# interface_dac_sma_feedback_3PS_ADC_detec.net
KiCad netlist of a schematic drawn in EAGLE
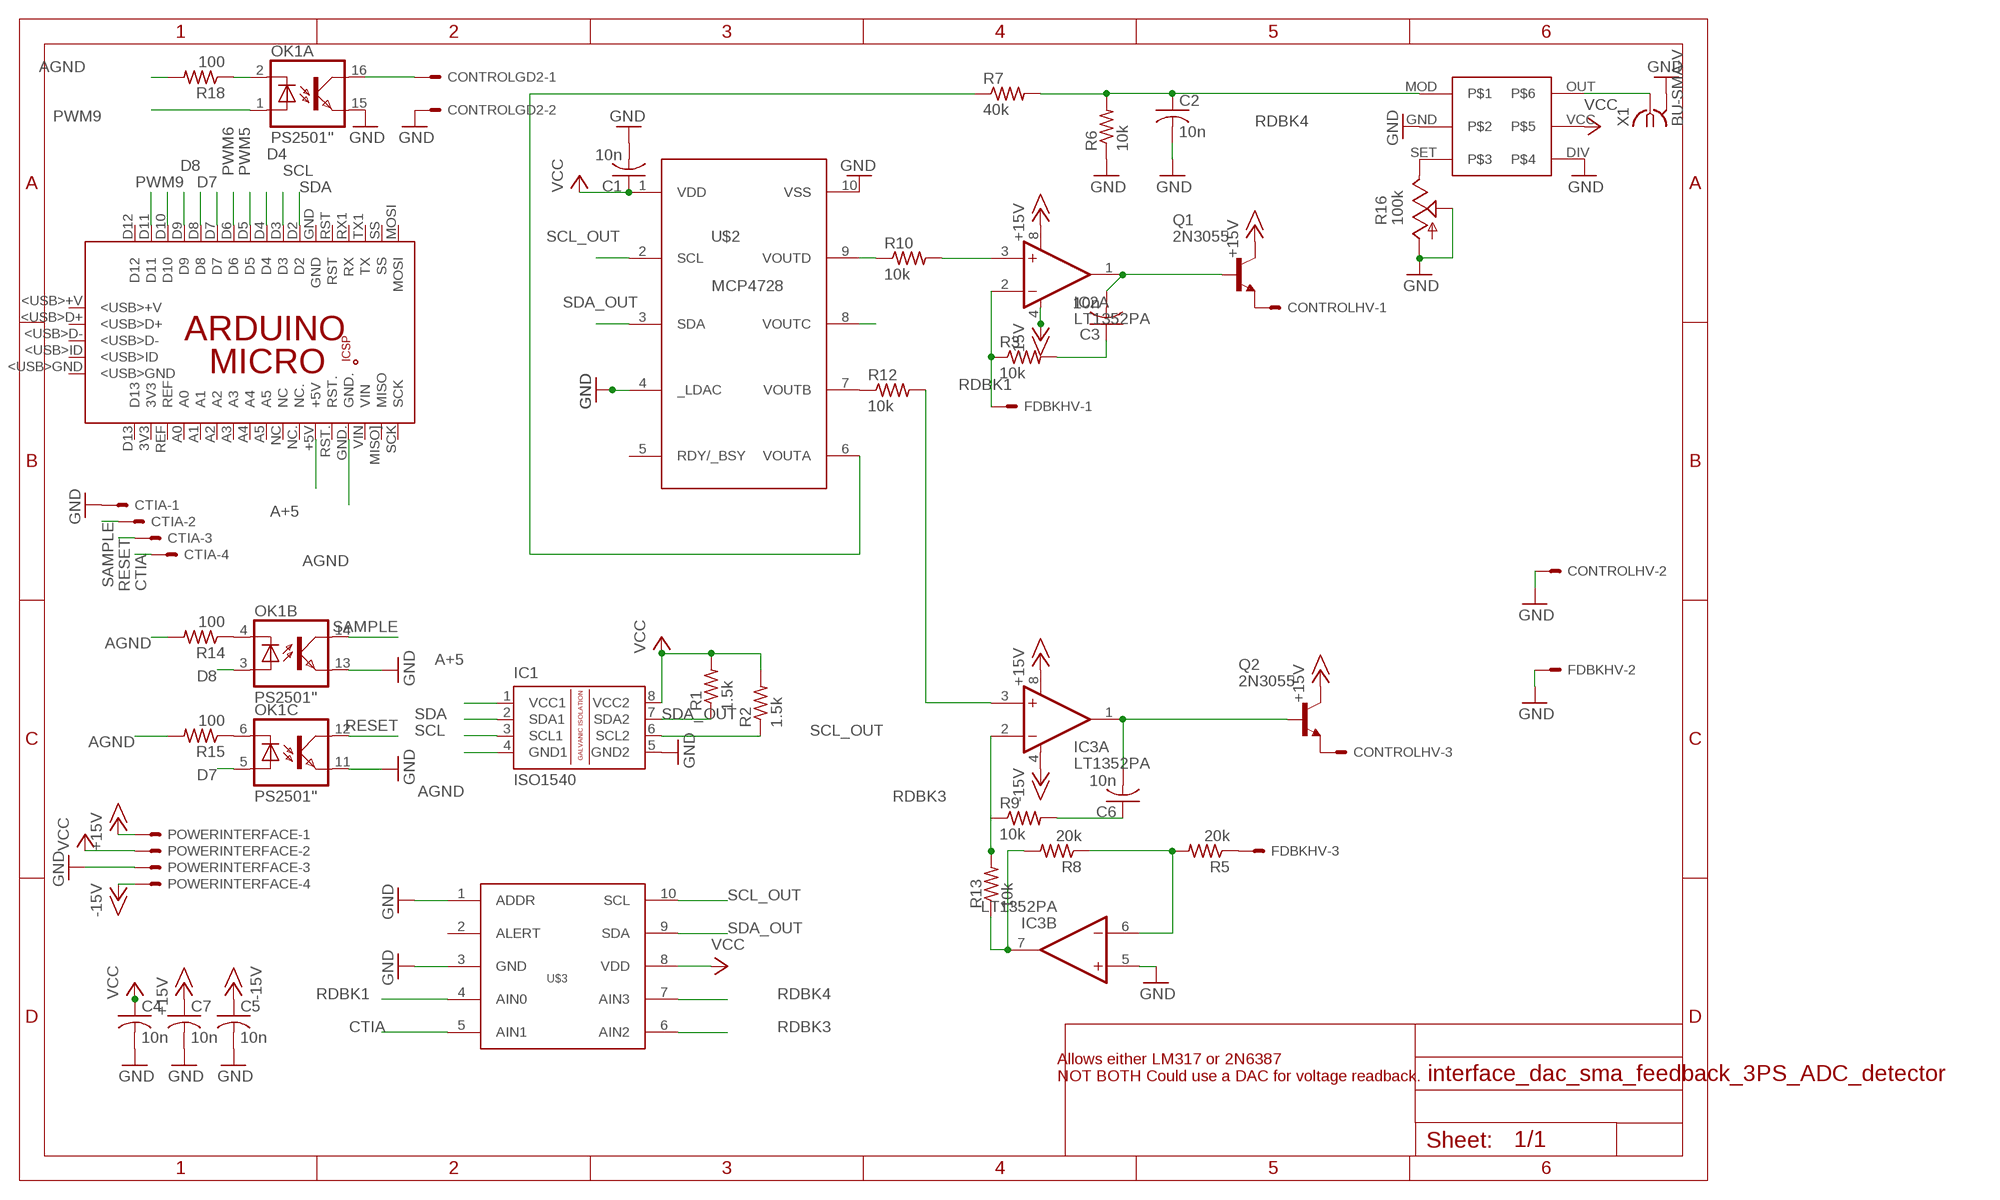
[diagram p0: schematic, sheet 1]

(export (version "E")
  (design (tool "Eeschema 10.0.6"))
  (components
    (comp (ref "C1")
      (value "10n")
      (footprint "eagle-import:C050-024X044")
      (libsource (lib "eagle-import") (part "C-US050-024X044"))
    )
    (comp (ref "C2")
      (value "10n")
      (footprint "eagle-import:C050-024X044")
      (libsource (lib "eagle-import") (part "resistor_C-US050-024X044"))
    )
    (comp (ref "C3")
      (value "10n")
      (footprint "eagle-import:C050-024X044")
      (libsource (lib "eagle-import") (part "resistor_C-US050-024X044"))
    )
    (comp (ref "C4")
      (value "10n")
      (footprint "eagle-import:C050-024X044")
      (libsource (lib "eagle-import") (part "resistor_C-US050-024X044"))
    )
    (comp (ref "C5")
      (value "10n")
      (footprint "eagle-import:C050-024X044")
      (libsource (lib "eagle-import") (part "resistor_C-US050-024X044"))
    )
    (comp (ref "C6")
      (value "10n")
      (footprint "eagle-import:C050-024X044")
      (libsource (lib "eagle-import") (part "resistor_C-US050-024X044"))
    )
    (comp (ref "C7")
      (value "10n")
      (footprint "eagle-import:C050-024X044")
      (libsource (lib "eagle-import") (part "resistor_C-US050-024X044"))
    )
    (comp (ref "CONTROLGD2")
      (value "KK-156-2")
      (footprint "eagle-import:KK-156-2")
      (libsource (lib "eagle-import") (part "KK-156-2"))
    )
    (comp (ref "CONTROLHV")
      (value "KK-156-3")
      (footprint "eagle-import:KK-156-3")
      (libsource (lib "eagle-import") (part "KK-156-3"))
    )
    (comp (ref "CTIA")
      (value "KK-156-4")
      (footprint "eagle-import:KK-156-4")
      (libsource (lib "eagle-import") (part "KK-156-4"))
    )
    (comp (ref "FDBKHV")
      (value "KK-156-3")
      (footprint "eagle-import:KK-156-3")
      (libsource (lib "eagle-import") (part "KK-156-3"))
    )
    (comp (ref "IC1")
      (value "ISO1540")
      (footprint "eagle-import:DIL08")
      (libsource (lib "eagle-import") (part "ISO1540"))
    )
    (comp (ref "IC2")
      (value "LT1352PA")
      (footprint "eagle-import:DIL08")
      (libsource (lib "eagle-import") (part "LT1352PA"))
    )
    (comp (ref "IC3")
      (value "LT1352PA")
      (footprint "eagle-import:DIL08")
      (libsource (lib "eagle-import") (part "LT1352PA"))
    )
    (comp (ref "OK1")
      (value "PS2501\"")
      (footprint "eagle-import:DIL16")
      (libsource (lib "eagle-import") (part "PS2501{dblquote}"))
    )
    (comp (ref "PCB1")
      (value "ARDUINO_MICRO")
      (footprint "eagle-import:ARDUINO_MICRO")
      (libsource (lib "eagle-import") (part "ARDUINO_MICRO"))
    )
    (comp (ref "POWERINTERFACE")
      (value "KK-156-4")
      (footprint "eagle-import:KK-156-4")
      (libsource (lib "eagle-import") (part "KK-156-4"))
    )
    (comp (ref "Q1")
      (value "2N3055")
      (footprint "eagle-import:TO3")
      (libsource (lib "eagle-import") (part "2N3055"))
    )
    (comp (ref "Q2")
      (value "2N3055")
      (footprint "eagle-import:TO3")
      (libsource (lib "eagle-import") (part "2N3055"))
    )
    (comp (ref "R1")
      (value "1.5k")
      (footprint "eagle-import:0207_12")
      (libsource (lib "eagle-import") (part "resistor_R-US_0207/12"))
    )
    (comp (ref "R2")
      (value "1.5k")
      (footprint "eagle-import:0207_12")
      (libsource (lib "eagle-import") (part "resistor_R-US_0207/12"))
    )
    (comp (ref "R3")
      (value "10k")
      (footprint "eagle-import:0207_12")
      (libsource (lib "eagle-import") (part "resistor_R-US_0207/12"))
    )
    (comp (ref "R5")
      (value "20k")
      (footprint "eagle-import:0207_12")
      (libsource (lib "eagle-import") (part "resistor_R-US_0207/12"))
    )
    (comp (ref "R6")
      (value "10k")
      (footprint "eagle-import:0207_12")
      (libsource (lib "eagle-import") (part "resistor_R-US_0207/12"))
    )
    (comp (ref "R7")
      (value "40k")
      (footprint "eagle-import:0207_12")
      (libsource (lib "eagle-import") (part "resistor_R-US_0207/12"))
    )
    (comp (ref "R8")
      (value "20k")
      (footprint "eagle-import:0207_12")
      (libsource (lib "eagle-import") (part "resistor_R-US_0207/12"))
    )
    (comp (ref "R9")
      (value "10k")
      (footprint "eagle-import:0207_12")
      (libsource (lib "eagle-import") (part "resistor_R-US_0207/12"))
    )
    (comp (ref "R10")
      (value "10k")
      (footprint "eagle-import:0207_12")
      (libsource (lib "eagle-import") (part "resistor_R-US_0207/12"))
    )
    (comp (ref "R12")
      (value "10k")
      (footprint "eagle-import:0207_12")
      (libsource (lib "eagle-import") (part "resistor_R-US_0207/12"))
    )
    (comp (ref "R13")
      (value "10k")
      (footprint "eagle-import:0207_12")
      (libsource (lib "eagle-import") (part "resistor_R-US_0207/12"))
    )
    (comp (ref "R14")
      (value "100")
      (footprint "eagle-import:0207_12")
      (libsource (lib "eagle-import") (part "R-US_0207/12"))
    )
    (comp (ref "R15")
      (value "100")
      (footprint "eagle-import:0207_12")
      (libsource (lib "eagle-import") (part "R-US_0207/12"))
    )
    (comp (ref "R16")
      (value "100k")
      (footprint "eagle-import:SP19L")
      (libsource (lib "eagle-import") (part "TRIM_US-B90P"))
    )
    (comp (ref "R18")
      (value "100")
      (footprint "eagle-import:0207_12")
      (libsource (lib "eagle-import") (part "R-US_0207/12"))
    )
    (comp (ref "U$1")
      (value "LTC6992")
      (footprint "eagle-import:DIL06")
      (libsource (lib "eagle-import") (part "LTC6992"))
    )
    (comp (ref "U$2")
      (value "MCP4728DIL")
      (footprint "eagle-import:DIL10")
      (libsource (lib "eagle-import") (part "MCP4728DIL"))
    )
    (comp (ref "U$3")
      (value "ADS1015DIL")
      (footprint "eagle-import:DIL10")
      (libsource (lib "eagle-import") (part "ADS1015DIL"))
    )
    (comp (ref "X1")
      (value "BU-SMA-V")
      (footprint "eagle-import:BU-SMA-V")
      (libsource (lib "eagle-import") (part "BU-SMA-V"))
    )
  )
  (nets
    (net (code "1") (name "+15V") (class "Default")
      (node (ref "C7") (pin "1") (pinfunction "1_1") (pintype "passive"))
      (node (ref "IC2") (pin "8") (pinfunction "V+_8") (pintype "power_in"))
      (node (ref "IC3") (pin "8") (pinfunction "V+_8") (pintype "power_in"))
      (node (ref "POWERINTERFACE") (pin "1") (pinfunction "S_1") (pintype "passive"))
      (node (ref "Q1") (pin "C") (pinfunction "C_C") (pintype "passive"))
      (node (ref "Q1") (pin "C/") (pinfunction "C_C/") (pintype "passive"))
      (node (ref "Q2") (pin "C") (pinfunction "C_C") (pintype "passive"))
      (node (ref "Q2") (pin "C/") (pinfunction "C_C/") (pintype "passive"))
    )
    (net (code "2") (name "-15V") (class "Default")
      (node (ref "C5") (pin "1") (pinfunction "1_1") (pintype "passive"))
      (node (ref "IC2") (pin "4") (pinfunction "V-_4") (pintype "power_in"))
      (node (ref "IC3") (pin "4") (pinfunction "V-_4") (pintype "power_in"))
      (node (ref "POWERINTERFACE") (pin "4") (pinfunction "S_4") (pintype "passive"))
    )
    (net (code "3") (name "/A+5") (class "Default")
      (node (ref "IC1") (pin "1") (pinfunction "VCC1_1") (pintype "input"))
      (node (ref "PCB1") (pin "+5V") (pinfunction "+5V_+5V") (pintype "bidirectional"))
    )
    (net (code "4") (name "/AGND") (class "Default")
      (node (ref "IC1") (pin "4") (pinfunction "GND1_4") (pintype "input"))
      (node (ref "PCB1") (pin "GND.") (pinfunction "GND._GND.") (pintype "bidirectional"))
      (node (ref "R14") (pin "2") (pinfunction "2_2") (pintype "passive"))
      (node (ref "R15") (pin "2") (pinfunction "2_2") (pintype "passive"))
      (node (ref "R18") (pin "2") (pinfunction "2_2") (pintype "passive"))
    )
    (net (code "5") (name "/CTIA") (class "Default")
      (node (ref "CTIA") (pin "4") (pinfunction "S_4") (pintype "passive"))
      (node (ref "U$3") (pin "5") (pinfunction "AIN1_5") (pintype "bidirectional"))
    )
    (net (code "6") (name "/D4") (class "Default")
      (node (ref "PCB1") (pin "D4") (pinfunction "D4_D4") (pintype "bidirectional"))
    )
    (net (code "7") (name "/D7") (class "Default")
      (node (ref "OK1") (pin "5") (pinfunction "A_5") (pintype "passive"))
      (node (ref "PCB1") (pin "D7") (pinfunction "D7_D7") (pintype "bidirectional"))
    )
    (net (code "8") (name "/D8") (class "Default")
      (node (ref "OK1") (pin "3") (pinfunction "A_3") (pintype "passive"))
      (node (ref "PCB1") (pin "D8") (pinfunction "D8_D8") (pintype "bidirectional"))
    )
    (net (code "9") (name "/PWM5") (class "Default")
      (node (ref "PCB1") (pin "D5") (pinfunction "D5_D5") (pintype "bidirectional"))
    )
    (net (code "10") (name "/PWM6") (class "Default")
      (node (ref "PCB1") (pin "D6") (pinfunction "D6_D6") (pintype "bidirectional"))
    )
    (net (code "11") (name "/PWM9") (class "Default")
      (node (ref "OK1") (pin "1") (pinfunction "A_1") (pintype "passive"))
      (node (ref "PCB1") (pin "D9") (pinfunction "D9_D9") (pintype "bidirectional"))
    )
    (net (code "12") (name "/RDBK1") (class "Default")
      (node (ref "FDBKHV") (pin "1") (pinfunction "S_1") (pintype "passive"))
      (node (ref "IC2") (pin "2") (pinfunction "-IN_2") (pintype "input"))
      (node (ref "R3") (pin "1") (pinfunction "1_1") (pintype "passive"))
      (node (ref "U$3") (pin "4") (pinfunction "AIN0_4") (pintype "bidirectional"))
    )
    (net (code "13") (name "/RDBK3") (class "Default")
      (node (ref "IC3") (pin "2") (pinfunction "-IN_2") (pintype "input"))
      (node (ref "R13") (pin "2") (pinfunction "2_2") (pintype "passive"))
      (node (ref "R9") (pin "1") (pinfunction "1_1") (pintype "passive"))
      (node (ref "U$3") (pin "6") (pinfunction "AIN2_6") (pintype "bidirectional"))
    )
    (net (code "14") (name "/RDBK4") (class "Default")
      (node (ref "C2") (pin "1") (pinfunction "1_1") (pintype "passive"))
      (node (ref "R6") (pin "2") (pinfunction "2_2") (pintype "passive"))
      (node (ref "R7") (pin "2") (pinfunction "2_2") (pintype "passive"))
      (node (ref "U$1") (pin "MOD") (pinfunction "P$1_MOD") (pintype "bidirectional"))
      (node (ref "U$3") (pin "7") (pinfunction "AIN3_7") (pintype "bidirectional"))
    )
    (net (code "15") (name "/RESET") (class "Default")
      (node (ref "CTIA") (pin "3") (pinfunction "S_3") (pintype "passive"))
      (node (ref "OK1") (pin "12") (pinfunction "COL_12") (pintype "passive"))
    )
    (net (code "16") (name "/SAMPLE") (class "Default")
      (node (ref "CTIA") (pin "2") (pinfunction "S_2") (pintype "passive"))
      (node (ref "OK1") (pin "14") (pinfunction "COL_14") (pintype "passive"))
    )
    (net (code "17") (name "/SCL") (class "Default")
      (node (ref "IC1") (pin "3") (pinfunction "SCL1_3") (pintype "input"))
      (node (ref "PCB1") (pin "D3") (pinfunction "D3_D3") (pintype "bidirectional"))
    )
    (net (code "18") (name "/SCL_OUT") (class "Default")
      (node (ref "IC1") (pin "6") (pinfunction "SCL2_6") (pintype "input"))
      (node (ref "R2") (pin "1") (pinfunction "1_1") (pintype "passive"))
      (node (ref "U$2") (pin "2") (pinfunction "SCL_2") (pintype "bidirectional"))
      (node (ref "U$3") (pin "10") (pinfunction "SCL_10") (pintype "bidirectional"))
    )
    (net (code "19") (name "/SDA") (class "Default")
      (node (ref "IC1") (pin "2") (pinfunction "SDA1_2") (pintype "input"))
      (node (ref "PCB1") (pin "D2") (pinfunction "D2_D2") (pintype "bidirectional"))
    )
    (net (code "20") (name "/SDA_OUT") (class "Default")
      (node (ref "IC1") (pin "7") (pinfunction "SDA2_7") (pintype "input"))
      (node (ref "R1") (pin "1") (pinfunction "1_1") (pintype "passive"))
      (node (ref "U$2") (pin "3") (pinfunction "SDA_3") (pintype "bidirectional"))
      (node (ref "U$3") (pin "9") (pinfunction "SDA_9") (pintype "bidirectional"))
    )
    (net (code "21") (name "GND") (class "Default")
      (node (ref "C1") (pin "2") (pinfunction "2_2") (pintype "passive"))
      (node (ref "C2") (pin "2") (pinfunction "2_2") (pintype "passive"))
      (node (ref "C4") (pin "2") (pinfunction "2_2") (pintype "passive"))
      (node (ref "C5") (pin "2") (pinfunction "2_2") (pintype "passive"))
      (node (ref "C7") (pin "2") (pinfunction "2_2") (pintype "passive"))
      (node (ref "CONTROLGD2") (pin "2") (pinfunction "S_2") (pintype "passive"))
      (node (ref "CONTROLHV") (pin "2") (pinfunction "S_2") (pintype "passive"))
      (node (ref "CTIA") (pin "1") (pinfunction "S_1") (pintype "passive"))
      (node (ref "FDBKHV") (pin "2") (pinfunction "S_2") (pintype "passive"))
      (node (ref "IC1") (pin "5") (pinfunction "GND2_5") (pintype "input"))
      (node (ref "IC3") (pin "5") (pinfunction "+IN_5") (pintype "input"))
      (node (ref "OK1") (pin "11") (pinfunction "EMI_11") (pintype "passive"))
      (node (ref "OK1") (pin "13") (pinfunction "EMI_13") (pintype "passive"))
      (node (ref "OK1") (pin "15") (pinfunction "EMI_15") (pintype "passive"))
      (node (ref "POWERINTERFACE") (pin "3") (pinfunction "S_3") (pintype "passive"))
      (node (ref "R16") (pin "A") (pinfunction "A_A") (pintype "passive"))
      (node (ref "R16") (pin "S") (pinfunction "S_S") (pintype "passive"))
      (node (ref "R6") (pin "1") (pinfunction "1_1") (pintype "passive"))
      (node (ref "U$1") (pin "DIV") (pinfunction "P$4_DIV") (pintype "bidirectional"))
      (node (ref "U$1") (pin "GND") (pinfunction "P$2_GND") (pintype "bidirectional"))
      (node (ref "U$2") (pin "10") (pinfunction "VSS_10") (pintype "bidirectional"))
      (node (ref "U$2") (pin "4") (pinfunction "_LDAC_4") (pintype "bidirectional"))
      (node (ref "U$3") (pin "1") (pinfunction "ADDR_1") (pintype "bidirectional"))
      (node (ref "U$3") (pin "3") (pinfunction "GND_3") (pintype "bidirectional"))
      (node (ref "X1") (pin "2") (pinfunction "2_2") (pintype "passive"))
      (node (ref "X1") (pin "3") (pinfunction "2_3") (pintype "passive"))
      (node (ref "X1") (pin "4") (pinfunction "2_4") (pintype "passive"))
      (node (ref "X1") (pin "5") (pinfunction "2_5") (pintype "passive"))
    )
    (net (code "22") (name "Net-(C3-Pad1)") (class "Default")
      (node (ref "C3") (pin "1") (pinfunction "1_1") (pintype "passive"))
      (node (ref "R3") (pin "2") (pinfunction "2_2") (pintype "passive"))
    )
    (net (code "23") (name "Net-(C6-Pad1)") (class "Default")
      (node (ref "C6") (pin "1") (pinfunction "1_1") (pintype "passive"))
      (node (ref "R9") (pin "2") (pinfunction "2_2") (pintype "passive"))
    )
    (net (code "24") (name "Net-(CONTROLGD2A-S)") (class "Default")
      (node (ref "CONTROLGD2") (pin "1") (pinfunction "S_1") (pintype "passive"))
      (node (ref "OK1") (pin "16") (pinfunction "COL_16") (pintype "passive"))
    )
    (net (code "25") (name "Net-(CONTROLHVA-S)") (class "Default")
      (node (ref "CONTROLHV") (pin "1") (pinfunction "S_1") (pintype "passive"))
      (node (ref "Q1") (pin "E") (pinfunction "E_E") (pintype "passive"))
    )
    (net (code "26") (name "Net-(CONTROLHVC-S)") (class "Default")
      (node (ref "CONTROLHV") (pin "3") (pinfunction "S_3") (pintype "passive"))
      (node (ref "Q2") (pin "E") (pinfunction "E_E") (pintype "passive"))
    )
    (net (code "27") (name "Net-(FDBKHVC-S)") (class "Default")
      (node (ref "FDBKHV") (pin "3") (pinfunction "S_3") (pintype "passive"))
      (node (ref "R5") (pin "1") (pinfunction "1_1") (pintype "passive"))
    )
    (net (code "28") (name "Net-(IC2A-+IN)") (class "Default")
      (node (ref "IC2") (pin "3") (pinfunction "+IN_3") (pintype "input"))
      (node (ref "R10") (pin "2") (pinfunction "2_2") (pintype "passive"))
    )
    (net (code "29") (name "Net-(IC2A-OUT)") (class "Default")
      (node (ref "C3") (pin "2") (pinfunction "2_2") (pintype "passive"))
      (node (ref "IC2") (pin "1") (pinfunction "OUT_1") (pintype "output"))
      (node (ref "Q1") (pin "B") (pinfunction "B_B") (pintype "passive"))
    )
    (net (code "30") (name "Net-(IC3A-+IN)") (class "Default")
      (node (ref "IC3") (pin "3") (pinfunction "+IN_3") (pintype "input"))
      (node (ref "R12") (pin "2") (pinfunction "2_2") (pintype "passive"))
    )
    (net (code "31") (name "Net-(IC3A-OUT)") (class "Default")
      (node (ref "C6") (pin "2") (pinfunction "2_2") (pintype "passive"))
      (node (ref "IC3") (pin "1") (pinfunction "OUT_1") (pintype "output"))
      (node (ref "Q2") (pin "B") (pinfunction "B_B") (pintype "passive"))
    )
    (net (code "32") (name "Net-(IC3B--IN)") (class "Default")
      (node (ref "IC3") (pin "6") (pinfunction "-IN_6") (pintype "input"))
      (node (ref "R5") (pin "2") (pinfunction "2_2") (pintype "passive"))
      (node (ref "R8") (pin "1") (pinfunction "1_1") (pintype "passive"))
    )
    (net (code "33") (name "Net-(IC3B-OUT)") (class "Default")
      (node (ref "IC3") (pin "7") (pinfunction "OUT_7") (pintype "output"))
      (node (ref "R13") (pin "1") (pinfunction "1_1") (pintype "passive"))
      (node (ref "R8") (pin "2") (pinfunction "2_2") (pintype "passive"))
    )
    (net (code "34") (name "Net-(OK1A-C)") (class "Default")
      (node (ref "OK1") (pin "2") (pinfunction "C_2") (pintype "passive"))
      (node (ref "R18") (pin "1") (pinfunction "1_1") (pintype "passive"))
    )
    (net (code "35") (name "Net-(OK1B-C)") (class "Default")
      (node (ref "OK1") (pin "4") (pinfunction "C_4") (pintype "passive"))
      (node (ref "R14") (pin "1") (pinfunction "1_1") (pintype "passive"))
    )
    (net (code "36") (name "Net-(OK1C-C)") (class "Default")
      (node (ref "OK1") (pin "6") (pinfunction "C_6") (pintype "passive"))
      (node (ref "R15") (pin "1") (pinfunction "1_1") (pintype "passive"))
    )
    (net (code "37") (name "Net-(U$1-P$3)") (class "Default")
      (node (ref "R16") (pin "E") (pinfunction "E_E") (pintype "passive"))
      (node (ref "U$1") (pin "SET") (pinfunction "P$3_SET") (pintype "bidirectional"))
    )
    (net (code "38") (name "Net-(U$1-P$6)") (class "Default")
      (node (ref "U$1") (pin "OUT") (pinfunction "P$6_OUT") (pintype "bidirectional"))
      (node (ref "X1") (pin "1") (pinfunction "1_1") (pintype "passive"))
    )
    (net (code "39") (name "Net-(U$2-VOUTA)") (class "Default")
      (node (ref "R7") (pin "1") (pinfunction "1_1") (pintype "passive"))
      (node (ref "U$2") (pin "6") (pinfunction "VOUTA_6") (pintype "bidirectional"))
    )
    (net (code "40") (name "Net-(U$2-VOUTB)") (class "Default")
      (node (ref "R12") (pin "1") (pinfunction "1_1") (pintype "passive"))
      (node (ref "U$2") (pin "7") (pinfunction "VOUTB_7") (pintype "bidirectional"))
    )
    (net (code "41") (name "Net-(U$2-VOUTD)") (class "Default")
      (node (ref "R10") (pin "1") (pinfunction "1_1") (pintype "passive"))
      (node (ref "U$2") (pin "9") (pinfunction "VOUTD_9") (pintype "bidirectional"))
    )
    (net (code "42") (name "VCC") (class "Default")
      (node (ref "C1") (pin "1") (pinfunction "1_1") (pintype "passive"))
      (node (ref "C4") (pin "1") (pinfunction "1_1") (pintype "passive"))
      (node (ref "IC1") (pin "8") (pinfunction "VCC2_8") (pintype "input"))
      (node (ref "POWERINTERFACE") (pin "2") (pinfunction "S_2") (pintype "passive"))
      (node (ref "R1") (pin "2") (pinfunction "2_2") (pintype "passive"))
      (node (ref "R2") (pin "2") (pinfunction "2_2") (pintype "passive"))
      (node (ref "U$1") (pin "VCC") (pinfunction "P$5_VCC") (pintype "bidirectional"))
      (node (ref "U$2") (pin "1") (pinfunction "VDD_1") (pintype "bidirectional"))
      (node (ref "U$3") (pin "8") (pinfunction "VDD_8") (pintype "bidirectional"))
    )
    (net (code "43") (name "unconnected-(PCB1-MISO-PadMISO])") (class "Default")
      (node (ref "PCB1") (pin "MISO]") (pinfunction "MISO_MISO]") (pintype "bidirectional"))
    )
    (net (code "44") (name "unconnected-(PCB1-Pad3V3)") (class "Default")
      (node (ref "PCB1") (pin "3V3") (pinfunction "3V3_3V3") (pintype "bidirectional"))
    )
    (net (code "45") (name "unconnected-(PCB1-Pad5V)") (class "Default")
      (node (ref "PCB1") (pin "5V") (pinfunction "5V_5V") (pintype "bidirectional"))
    )
    (net (code "46") (name "unconnected-(PCB1-Pad<USB>+V)") (class "Default")
      (node (ref "PCB1") (pin "<USB>+V") (pinfunction "<USB>+V_<USB>+V") (pintype "bidirectional"))
    )
    (net (code "47") (name "unconnected-(PCB1-Pad<USB>D+)") (class "Default")
      (node (ref "PCB1") (pin "<USB>D+") (pinfunction "<USB>D+_<USB>D+") (pintype "bidirectional"))
    )
    (net (code "48") (name "unconnected-(PCB1-Pad<USB>D-)") (class "Default")
      (node (ref "PCB1") (pin "<USB>D-") (pinfunction "<USB>D-_<USB>D-") (pintype "bidirectional"))
    )
    (net (code "49") (name "unconnected-(PCB1-Pad<USB>GND)") (class "Default")
      (node (ref "PCB1") (pin "<USB>GND") (pinfunction "<USB>GND_<USB>GND") (pintype "bidirectional"))
    )
    (net (code "50") (name "unconnected-(PCB1-Pad<USB>ID)") (class "Default")
      (node (ref "PCB1") (pin "<USB>ID") (pinfunction "<USB>ID_<USB>ID") (pintype "bidirectional"))
    )
    (net (code "51") (name "unconnected-(PCB1-PadA0)") (class "Default")
      (node (ref "PCB1") (pin "A0") (pinfunction "A0_A0") (pintype "bidirectional"))
    )
    (net (code "52") (name "unconnected-(PCB1-PadA1)") (class "Default")
      (node (ref "PCB1") (pin "A1") (pinfunction "A1_A1") (pintype "bidirectional"))
    )
    (net (code "53") (name "unconnected-(PCB1-PadA2)") (class "Default")
      (node (ref "PCB1") (pin "A2") (pinfunction "A2_A2") (pintype "bidirectional"))
    )
    (net (code "54") (name "unconnected-(PCB1-PadA3)") (class "Default")
      (node (ref "PCB1") (pin "A3") (pinfunction "A3_A3") (pintype "bidirectional"))
    )
    (net (code "55") (name "unconnected-(PCB1-PadA4)") (class "Default")
      (node (ref "PCB1") (pin "A4") (pinfunction "A4_A4") (pintype "bidirectional"))
    )
    (net (code "56") (name "unconnected-(PCB1-PadA5)") (class "Default")
      (node (ref "PCB1") (pin "A5") (pinfunction "A5_A5") (pintype "bidirectional"))
    )
    (net (code "57") (name "unconnected-(PCB1-PadD10)") (class "Default")
      (node (ref "PCB1") (pin "D10") (pinfunction "D10_D10") (pintype "bidirectional"))
    )
    (net (code "58") (name "unconnected-(PCB1-PadD11)") (class "Default")
      (node (ref "PCB1") (pin "D11") (pinfunction "D11_D11") (pintype "bidirectional"))
    )
    (net (code "59") (name "unconnected-(PCB1-PadD12)") (class "Default")
      (node (ref "PCB1") (pin "D12") (pinfunction "D12_D12") (pintype "bidirectional"))
    )
    (net (code "60") (name "unconnected-(PCB1-PadD13)") (class "Default")
      (node (ref "PCB1") (pin "D13") (pinfunction "D13_D13") (pintype "bidirectional"))
    )
    (net (code "61") (name "unconnected-(PCB1-PadGND)") (class "Default")
      (node (ref "PCB1") (pin "GND") (pinfunction "GND_GND") (pintype "bidirectional"))
    )
    (net (code "62") (name "unconnected-(PCB1-PadGND_)") (class "Default")
      (node (ref "PCB1") (pin "GND_") (pinfunction "GND__GND_") (pintype "bidirectional"))
    )
    (net (code "63") (name "unconnected-(PCB1-PadMISO.)") (class "Default")
      (node (ref "PCB1") (pin "MISO.") (pinfunction "MISO._MISO.") (pintype "bidirectional"))
    )
    (net (code "64") (name "unconnected-(PCB1-PadMOSI)") (class "Default")
      (node (ref "PCB1") (pin "MOSI") (pinfunction "MOSI_MOSI") (pintype "bidirectional"))
    )
    (net (code "65") (name "unconnected-(PCB1-PadMOSI.)") (class "Default")
      (node (ref "PCB1") (pin "MOSI.") (pinfunction "MOSI._MOSI.") (pintype "bidirectional"))
    )
    (net (code "66") (name "unconnected-(PCB1-PadNC)") (class "Default")
      (node (ref "PCB1") (pin "NC") (pinfunction "NC_NC") (pintype "bidirectional"))
    )
    (net (code "67") (name "unconnected-(PCB1-PadNC.)") (class "Default")
      (node (ref "PCB1") (pin "NC.") (pinfunction "NC._NC.") (pintype "bidirectional"))
    )
    (net (code "68") (name "unconnected-(PCB1-PadREF)") (class "Default")
      (node (ref "PCB1") (pin "REF") (pinfunction "REF_REF") (pintype "bidirectional"))
    )
    (net (code "69") (name "unconnected-(PCB1-PadRESET..)") (class "Default")
      (node (ref "PCB1") (pin "RESET..") (pinfunction "RESET.._RESET..") (pintype "bidirectional"))
    )
    (net (code "70") (name "unconnected-(PCB1-PadRST)") (class "Default")
      (node (ref "PCB1") (pin "RST") (pinfunction "RST_RST") (pintype "bidirectional"))
    )
    (net (code "71") (name "unconnected-(PCB1-PadRST.)") (class "Default")
      (node (ref "PCB1") (pin "RST.") (pinfunction "RST._RST.") (pintype "bidirectional"))
    )
    (net (code "72") (name "unconnected-(PCB1-PadSCK)") (class "Default")
      (node (ref "PCB1") (pin "SCK") (pinfunction "SCK_SCK") (pintype "bidirectional"))
    )
    (net (code "73") (name "unconnected-(PCB1-PadSCK.)") (class "Default")
      (node (ref "PCB1") (pin "SCK.") (pinfunction "SCK._SCK.") (pintype "bidirectional"))
    )
    (net (code "74") (name "unconnected-(PCB1-PadSS)") (class "Default")
      (node (ref "PCB1") (pin "SS") (pinfunction "SS_SS") (pintype "bidirectional"))
    )
    (net (code "75") (name "unconnected-(PCB1-PadVIN)") (class "Default")
      (node (ref "PCB1") (pin "VIN") (pinfunction "VIN_VIN") (pintype "bidirectional"))
    )
    (net (code "76") (name "unconnected-(PCB1-RX-PadRX1)") (class "Default")
      (node (ref "PCB1") (pin "RX1") (pinfunction "RX_RX1") (pintype "bidirectional"))
    )
    (net (code "77") (name "unconnected-(PCB1-TX-PadTX1)") (class "Default")
      (node (ref "PCB1") (pin "TX1") (pinfunction "TX_TX1") (pintype "bidirectional"))
    )
    (net (code "78") (name "unconnected-(U$2-RDY{slash}_BSY-Pad5)") (class "Default")
      (node (ref "U$2") (pin "5") (pinfunction "RDY/_BSY_5") (pintype "bidirectional"))
    )
    (net (code "79") (name "unconnected-(U$2-VOUTC-Pad8)") (class "Default")
      (node (ref "U$2") (pin "8") (pinfunction "VOUTC_8") (pintype "bidirectional"))
    )
    (net (code "80") (name "unconnected-(U$3-ALERT-Pad2)") (class "Default")
      (node (ref "U$3") (pin "2") (pinfunction "ALERT_2") (pintype "bidirectional"))
    )
  )
)
